# MicroDial_Data_Log_V2_Part3.net
KiCad netlist of a schematic drawn in Altium Designer
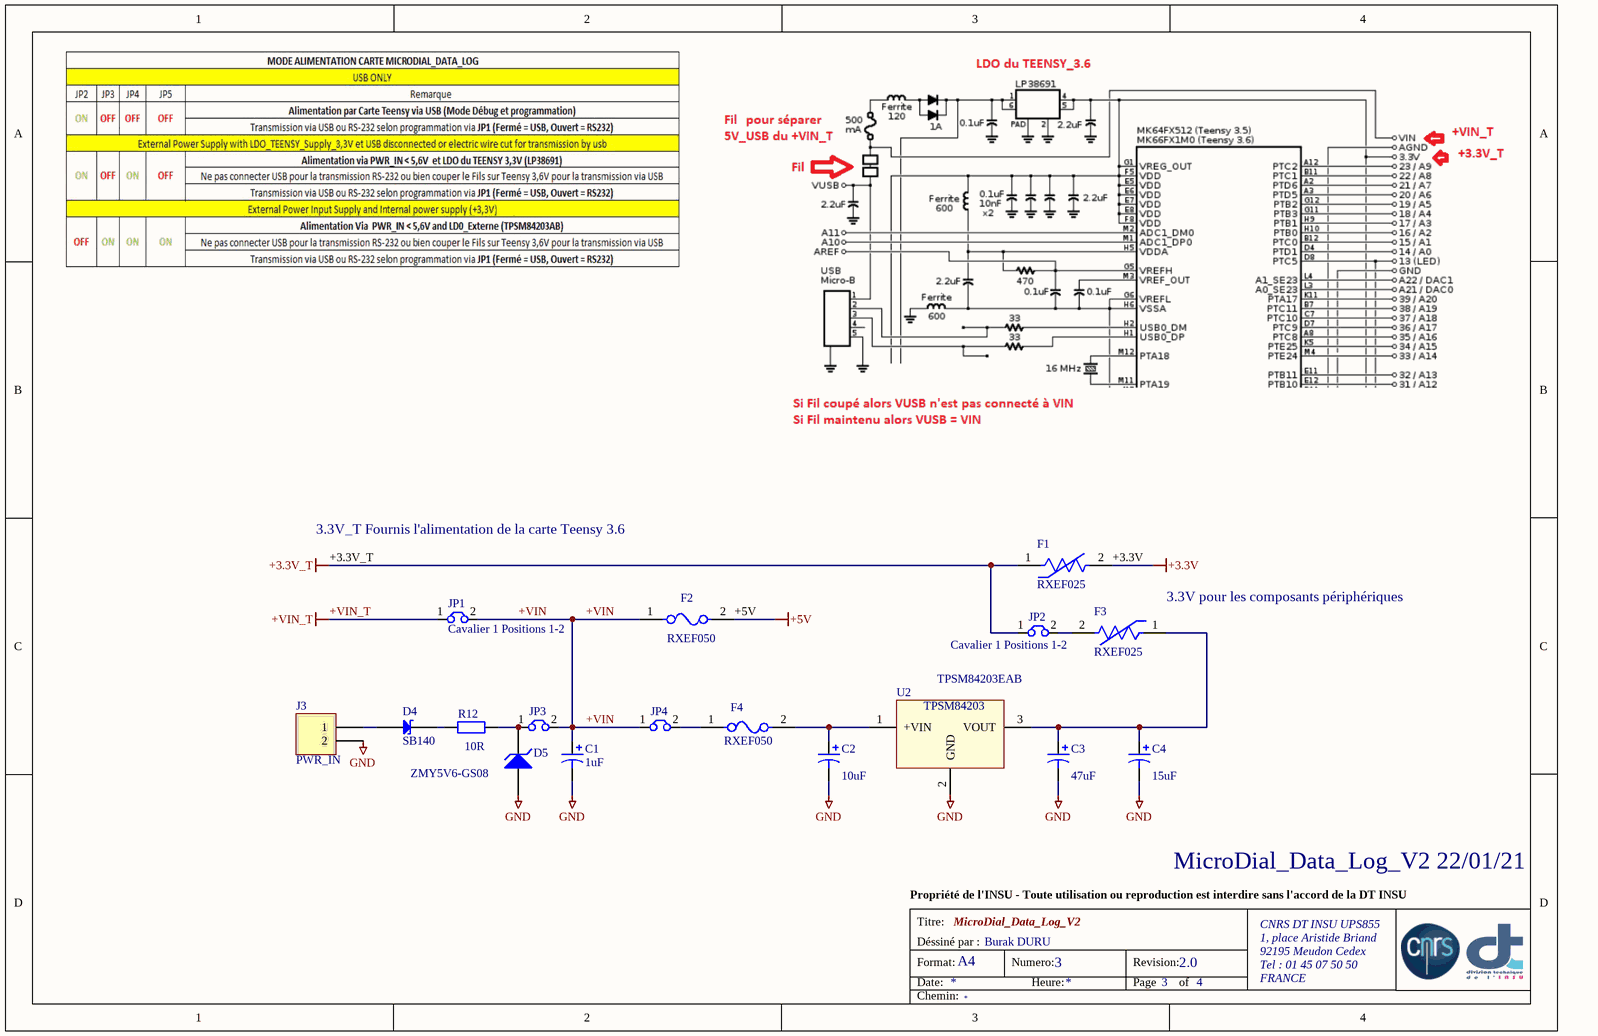
[diagram p0: MicroDial_Data_Log_V2_Part3.SchDoc]

(export (version "E")
  (design (tool "Eeschema 10.0.6"))
  (components
    (comp (ref "C1")
      (value "1uF")
      (footprint "CAPPR5-10*x11.5")
      (description "Condensateur Nichicon, 1μF, 450V c.c., série PS")
      (libsource (lib "pSDLA") (part "Cap  Aluminuim Pol"))
    )
    (comp (ref "C2")
      (value "10uF")
      (footprint "CAPA-B")
      (fields (field (name "Comment") "Polarized Capacitor Tantale"))
      (libsource (lib "pSDLA") (part "Cap Tantale Pol"))
    )
    (comp (ref "C3")
      (value "47uF")
      (footprint "CAPA-B")
      (fields (field (name "Comment") "Polarized Capacitor Tantale"))
      (libsource (lib "pSDLA") (part "Cap Tantale Pol"))
    )
    (comp (ref "C4")
      (value "15uF")
      (footprint "CAPA-D")
      (fields (field (name "Comment") "Polarized Capacitor Tantale"))
      (libsource (lib "pSDLA") (part "Cap Tantale Pol"))
    )
    (comp (ref "D4")
      (value "SB140")
      (footprint "DO-41")
      (description "SB140 Redresseur Schottky, 40 V, 1 A, Une, DO-41 (DO-204AL), 2 Broche(s), 500 mV")
      (libsource (lib "pSDLA") (part "Diode_Schottky"))
    )
    (comp (ref "D5")
      (value "ZMY5V6-GS08")
      (footprint "MELF DO-213AB")
      (description "ZMY5V6-GS08 Diode simple Zener, AEC-Q101, 5.6 V, 1 W, MELF, 2 Broche(s), 175 °C")
      (libsource (lib "MicroDial") (part "ZMY5V6-GS08"))
    )
    (comp (ref "F1")
      (value "RXEF025")
      (footprint "FP-RXEF025-MFG")
      (description "RXEF025 -  FUSE, PTC RESET, 72V, 250mA, RADIAL")
      (libsource (lib "MicroDial_Stagiare") (part "RXEF025"))
    )
    (comp (ref "F2")
      (value "RXEF050")
      (footprint "FP-RXEF050-MFG")
      (libsource (lib "MicroDial_Stagiare") (part "RXEF050"))
    )
    (comp (ref "F3")
      (value "RXEF025")
      (footprint "FP-RXEF025-MFG")
      (description "RXEF025 -  FUSE, PTC RESET, 72V, 250mA, RADIAL")
      (libsource (lib "MicroDial_Stagiare") (part "RXEF025"))
    )
    (comp (ref "F4")
      (value "RXEF050")
      (footprint "FP-RXEF050-MFG")
      (libsource (lib "MicroDial_Stagiare") (part "RXEF050"))
    )
    (comp (ref "J3")
      (value "PWR_IN")
      (footprint "SL 3.5/2/90G")
      (description "WEIDMULLER SL 3.5/2/90B SR 2V COUDE")
      (libsource (lib "pSDLA") (part "WEIDMULLER SL 3.5/2/90G"))
    )
    (comp (ref "JP1")
      (value "Cavalier 1 Positions 1-2")
      (footprint "Molex 90120-0762")
      (description "Jumper 2 Wire")
      (libsource (lib "pSDLA") (part "Jump 12"))
    )
    (comp (ref "JP2")
      (value "Cavalier 1 Positions 1-2")
      (footprint "Molex 90120-0762")
      (description "Jumper 2 Wire")
      (libsource (lib "pSDLA") (part "Jump 12"))
    )
    (comp (ref "JP3")
      (value "Cavalier 1 Positions 1-2")
      (footprint "Molex 90120-0762")
      (description "Jumper 2 Wire")
      (libsource (lib "pSDLA") (part "Jump 12"))
    )
    (comp (ref "JP4")
      (value "Cavalier 1 Positions 1-2")
      (footprint "Molex 90120-0762")
      (description "Jumper 2 Wire")
      (libsource (lib "pSDLA") (part "Jump 12"))
    )
    (comp (ref "R12")
      (value "10R")
      (footprint "R1206")
      (fields (field (name "Comment") "Res"))
      (libsource (lib "pSDLA") (part "Res"))
    )
    (comp (ref "U2")
      (value "TPSM84203EAB")
      (footprint "TPSM842XX SIPMODULE")
      (description "TPSM84203EAB -  Convertisseur DC/DC, 1 sortie, 4.95 W, 3.3 V, 1.5 A, TPSM842xx Family")
      (libsource (lib "MicroDial_Stagiare") (part "TPSM84203EAB"))
    )
  )
  (nets
    (net (code "1") (name "+3.3V") (class "Default")
      (node (ref "F1") (pin "2") (pinfunction "2_2") (pintype "passive"))
    )
    (net (code "2") (name "+3.3V_T") (class "Default")
      (node (ref "F1") (pin "1") (pinfunction "1_1") (pintype "passive"))
      (node (ref "JP2") (pin "1") (pinfunction "1_1") (pintype "passive"))
    )
    (net (code "3") (name "+5V") (class "Default")
      (node (ref "F2") (pin "2") (pinfunction "2_2") (pintype "passive"))
    )
    (net (code "4") (name "+VIN_T") (class "Default")
      (node (ref "JP1") (pin "1") (pinfunction "1_1") (pintype "passive"))
    )
    (net (code "5") (name "/+VIN") (class "Default")
      (node (ref "C1") (pin "1") (pinfunction "1_1") (pintype "passive"))
      (node (ref "F2") (pin "1") (pinfunction "1_1") (pintype "passive"))
      (node (ref "JP1") (pin "2") (pinfunction "2_2") (pintype "passive"))
      (node (ref "JP3") (pin "2") (pinfunction "2_2") (pintype "passive"))
      (node (ref "JP4") (pin "1") (pinfunction "1_1") (pintype "passive"))
    )
    (net (code "6") (name "GND") (class "Default")
      (node (ref "C1") (pin "2") (pinfunction "2_2") (pintype "passive"))
      (node (ref "C2") (pin "2") (pinfunction "2_2") (pintype "passive"))
      (node (ref "C3") (pin "2") (pinfunction "2_2") (pintype "passive"))
      (node (ref "C4") (pin "2") (pinfunction "2_2") (pintype "passive"))
      (node (ref "D5") (pin "1") (pinfunction "A_1") (pintype "passive"))
      (node (ref "J3") (pin "2") (pinfunction "2_2") (pintype "passive"))
      (node (ref "U2") (pin "2") (pinfunction "GND_2") (pintype "passive"))
    )
    (net (code "7") (name "Net-(D4-A)") (class "Default")
      (node (ref "D4") (pin "1") (pinfunction "A_1") (pintype "passive"))
      (node (ref "J3") (pin "1") (pinfunction "1_1") (pintype "passive"))
    )
    (net (code "8") (name "Net-(D4-K)") (class "Default")
      (node (ref "D4") (pin "2") (pinfunction "K_2") (pintype "passive"))
      (node (ref "R12") (pin "1") (pinfunction "1_1") (pintype "passive"))
    )
    (net (code "9") (name "Net-(D5-K)") (class "Default")
      (node (ref "D5") (pin "2") (pinfunction "K_2") (pintype "passive"))
      (node (ref "JP3") (pin "1") (pinfunction "1_1") (pintype "passive"))
      (node (ref "R12") (pin "2") (pinfunction "2_2") (pintype "passive"))
    )
    (net (code "10") (name "Net-(F3-Pad2)") (class "Default")
      (node (ref "F3") (pin "2") (pinfunction "2_2") (pintype "passive"))
      (node (ref "JP2") (pin "2") (pinfunction "2_2") (pintype "passive"))
    )
    (net (code "11") (name "Net-(F4-Pad1)") (class "Default")
      (node (ref "F4") (pin "1") (pinfunction "1_1") (pintype "passive"))
      (node (ref "JP4") (pin "2") (pinfunction "2_2") (pintype "passive"))
    )
    (net (code "12") (name "Net-(U2-+VIN)") (class "Default")
      (node (ref "C2") (pin "1") (pinfunction "1_1") (pintype "passive"))
      (node (ref "F4") (pin "2") (pinfunction "2_2") (pintype "passive"))
      (node (ref "U2") (pin "1") (pinfunction "+VIN_1") (pintype "passive"))
    )
    (net (code "13") (name "Net-(U2-VOUT)") (class "Default")
      (node (ref "C3") (pin "1") (pinfunction "1_1") (pintype "passive"))
      (node (ref "C4") (pin "1") (pinfunction "1_1") (pintype "passive"))
      (node (ref "F3") (pin "1") (pinfunction "1_1") (pintype "passive"))
      (node (ref "U2") (pin "3") (pinfunction "VOUT_3") (pintype "passive"))
    )
  )
)
